# lamloei_app_a092508.net
KiCad netlist of a schematic drawn in EAGLE
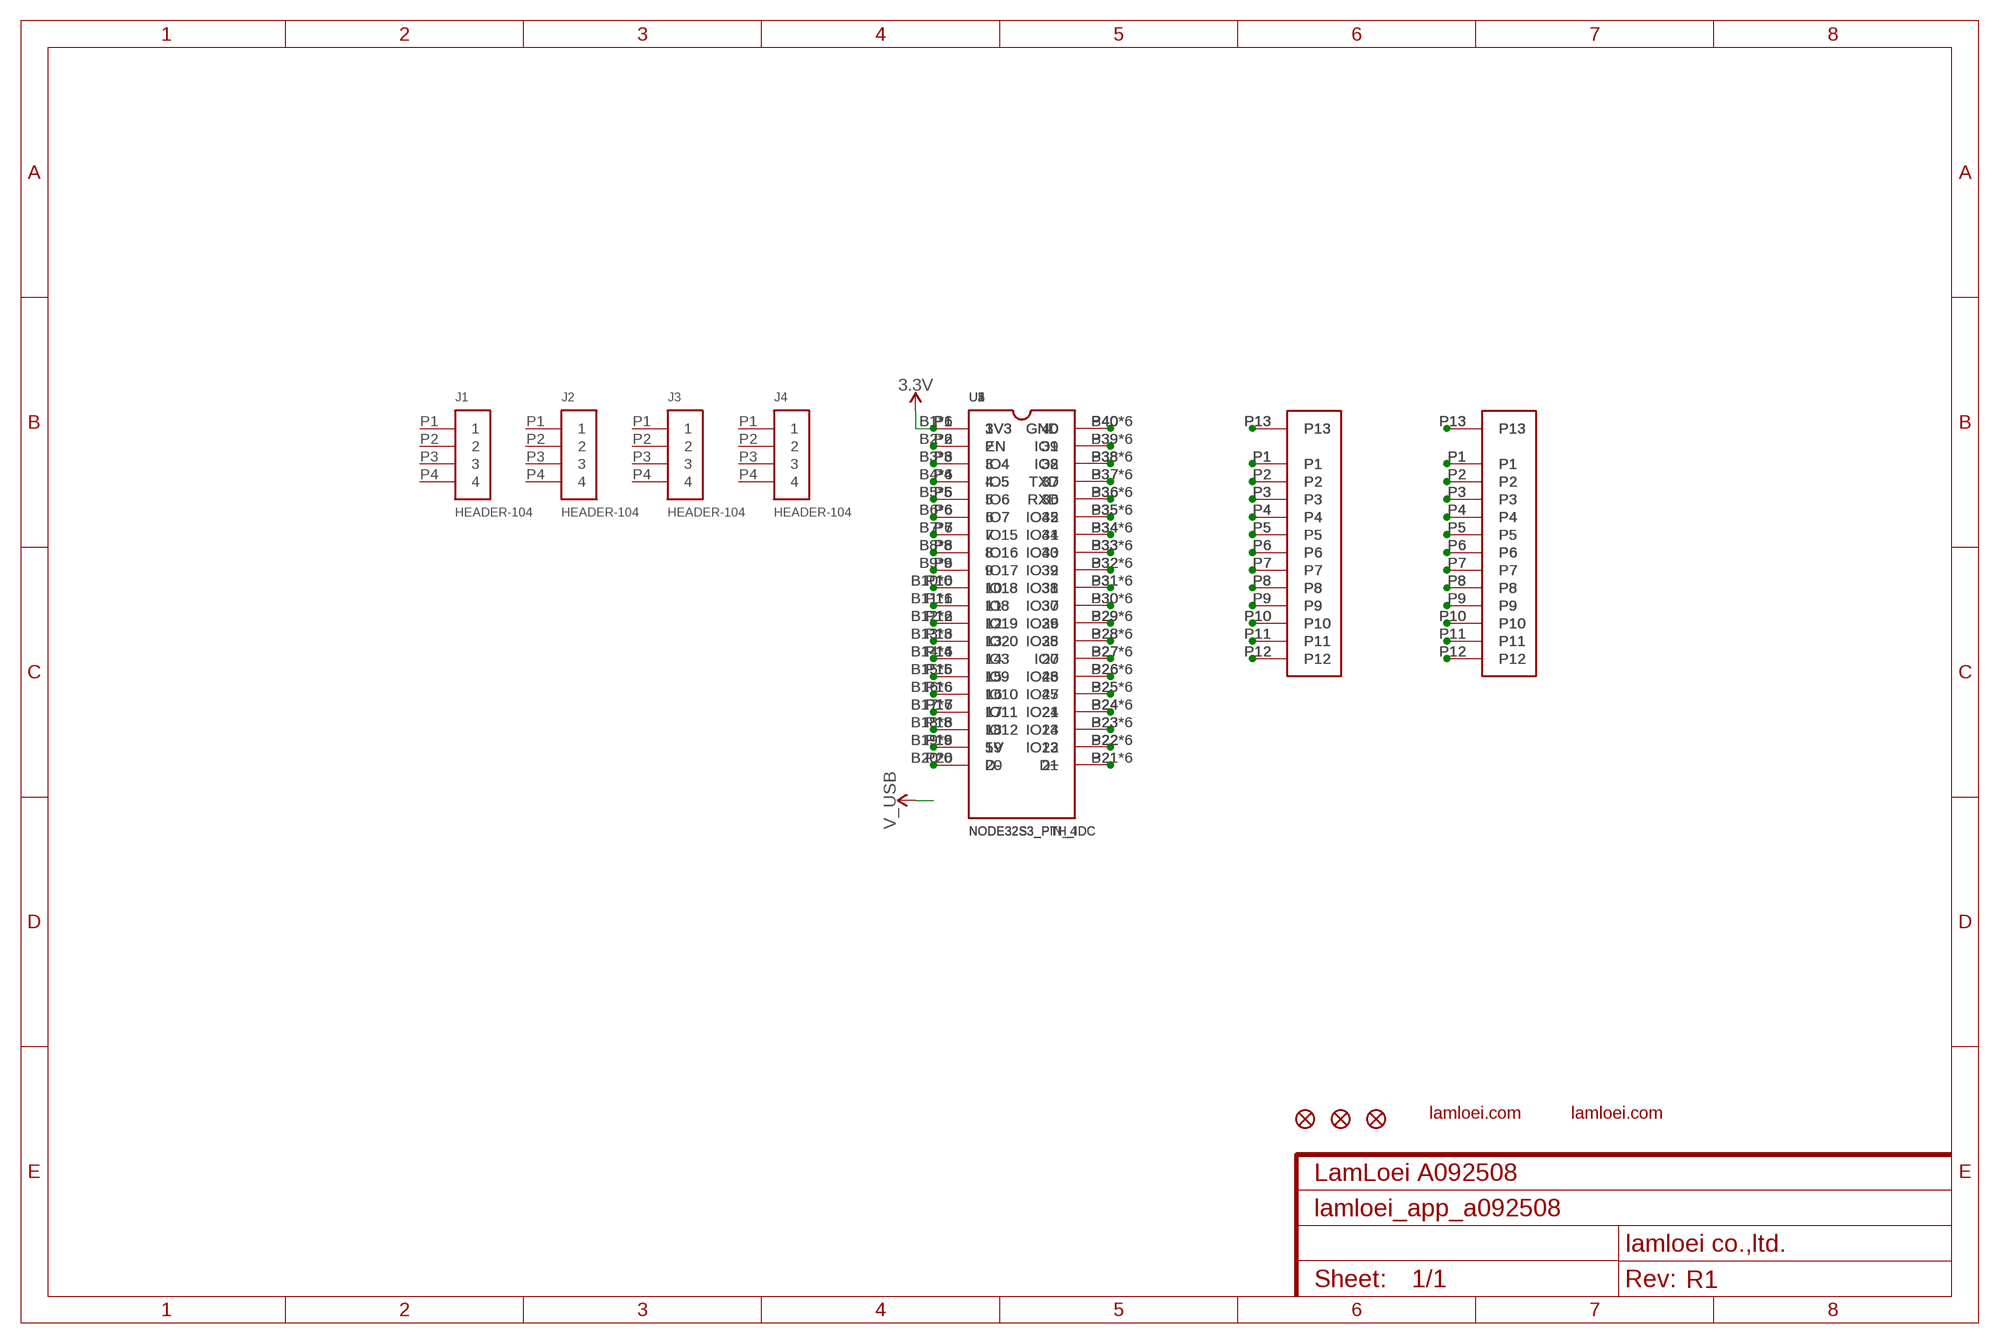
[diagram p0: schematic, sheet 1]

(export (version "E")
  (design (tool "Eeschema 10.0.6"))
  (components
    (comp (ref "J1")
      (value "HEADER-104")
      (footprint "eagle-import:HEADER-104")
      (libsource (lib "eagle-import") (part "HEADER-104"))
    )
    (comp (ref "J2")
      (value "HEADER-104")
      (footprint "eagle-import:HEADER-104")
      (libsource (lib "eagle-import") (part "HEADER-104"))
    )
    (comp (ref "J3")
      (value "HEADER-104")
      (footprint "eagle-import:HEADER-104")
      (libsource (lib "eagle-import") (part "HEADER-104"))
    )
    (comp (ref "J4")
      (value "HEADER-104")
      (footprint "eagle-import:HEADER-104")
      (libsource (lib "eagle-import") (part "HEADER-104"))
    )
    (comp (ref "U1")
      (value "NODE32S3_PIN_4")
      (footprint "eagle-import:NODE32S3_PTH_4")
      (libsource (lib "eagle-import") (part "NODE32S3_PIN_4"))
    )
    (comp (ref "U2")
      (value "NODE32S3_PIN_4")
      (footprint "eagle-import:NODE32S3_PTH_4")
      (libsource (lib "eagle-import") (part "NODE32S3_PIN_4"))
    )
    (comp (ref "U3")
      (value "NODE32S3_PTH_IDC")
      (footprint "eagle-import:NODE32S3_PTH_IDC")
      (libsource (lib "eagle-import") (part "NODE32S3_PTH_IDC"))
    )
    (comp (ref "U4")
      (value "NODE32S3_PTH_IDC")
      (footprint "eagle-import:NODE32S3_PTH_IDC")
      (libsource (lib "eagle-import") (part "NODE32S3_PTH_IDC"))
    )
    (comp (ref "U5")
      (value "NODE32S3_PTH_IDC")
      (footprint "eagle-import:NODE32S3_PTH_IDC")
      (libsource (lib "eagle-import") (part "NODE32S3_PTH_IDC"))
    )
    (comp (ref "X1")
      (value "5EHDRC-12P-508")
      (footprint "eagle-import:5EHDRC-12P-508")
      (libsource (lib "eagle-import") (part "5EHDRC-12P-508"))
    )
    (comp (ref "X2")
      (value "5EHDRC-12P-5.08MM")
      (footprint "eagle-import:5EHDRC-12P-5.08MM")
      (libsource (lib "eagle-import") (part "5EHDRC-12P-5.08MM"))
    )
    (comp (ref "X3")
      (value "5EHDRC-12P-2-508")
      (footprint "eagle-import:5EHDRC-12P-2-508")
      (libsource (lib "eagle-import") (part "5EHDRC-12P-2-508"))
    )
    (comp (ref "X4")
      (value "5EHDRC-12P-508")
      (footprint "eagle-import:5EHDRC-12P-508")
      (libsource (lib "eagle-import") (part "5EHDRC-12P-508"))
    )
    (comp (ref "X5")
      (value "5EHDRC-12P-5.08MM")
      (footprint "eagle-import:5EHDRC-12P-5.08MM")
      (libsource (lib "eagle-import") (part "5EHDRC-12P-5.08MM"))
    )
    (comp (ref "X6")
      (value "5EHDRC-12P-2-508")
      (footprint "eagle-import:5EHDRC-12P-2-508")
      (libsource (lib "eagle-import") (part "5EHDRC-12P-2-508"))
    )
    (comp (ref "ZFD1")
      (value "FIDUCIAL1X2")
      (footprint "eagle-import:FIDUCIAL-1X2")
      (libsource (lib "eagle-import") (part "FIDUCIAL1X2"))
    )
    (comp (ref "ZFD2")
      (value "FIDUCIAL1X2")
      (footprint "eagle-import:FIDUCIAL-1X2")
      (libsource (lib "eagle-import") (part "FIDUCIAL1X2"))
    )
    (comp (ref "ZFD3")
      (value "FIDUCIAL1X2")
      (footprint "eagle-import:FIDUCIAL-1X2")
      (libsource (lib "eagle-import") (part "FIDUCIAL1X2"))
    )
    (comp (ref "ZL1")
      (value "LAMLEOI_LOGO_3")
      (footprint "eagle-import:LAMLEOI_LOGO_3")
      (libsource (lib "eagle-import") (part "LAMLEOI_LOGO_3"))
    )
    (comp (ref "ZL2")
      (value "LAMLEOI_LOGO_3")
      (footprint "eagle-import:LAMLEOI_LOGO_3")
      (libsource (lib "eagle-import") (part "LAMLEOI_LOGO_3"))
    )
  )
  (nets
    (net (code "1") (name "3.3V") (class "Default")
      (node (ref "U1") (pin "B1") (pinfunction "1_B1") (pintype "bidirectional"))
      (node (ref "U1") (pin "N1") (pinfunction "1_N1") (pintype "bidirectional"))
      (node (ref "U1") (pin "O1") (pinfunction "1_O1") (pintype "bidirectional"))
      (node (ref "U1") (pin "P1") (pinfunction "1_P1") (pintype "bidirectional"))
      (node (ref "U1") (pin "Q1") (pinfunction "1_Q1") (pintype "bidirectional"))
      (node (ref "U1") (pin "T1") (pinfunction "1_T1") (pintype "bidirectional"))
      (node (ref "U2") (pin "B1") (pinfunction "1_B1") (pintype "bidirectional"))
      (node (ref "U2") (pin "N1") (pinfunction "1_N1") (pintype "bidirectional"))
      (node (ref "U2") (pin "O1") (pinfunction "1_O1") (pintype "bidirectional"))
      (node (ref "U2") (pin "P1") (pinfunction "1_P1") (pintype "bidirectional"))
      (node (ref "U2") (pin "Q1") (pinfunction "1_Q1") (pintype "bidirectional"))
      (node (ref "U2") (pin "T1") (pinfunction "1_T1") (pintype "bidirectional"))
      (node (ref "U3") (pin "P1") (pinfunction "3V3_P1") (pintype "bidirectional"))
      (node (ref "U4") (pin "P1") (pinfunction "3V3_P1") (pintype "bidirectional"))
      (node (ref "U5") (pin "P1") (pinfunction "3V3_P1") (pintype "bidirectional"))
    )
    (net (code "2") (name "Net-(U3-5V)") (class "Default")
      (node (ref "U1") (pin "B19") (pinfunction "19_B19") (pintype "bidirectional"))
      (node (ref "U1") (pin "N19") (pinfunction "19_N19") (pintype "bidirectional"))
      (node (ref "U1") (pin "O19") (pinfunction "19_O19") (pintype "bidirectional"))
      (node (ref "U1") (pin "P19") (pinfunction "19_P19") (pintype "bidirectional"))
      (node (ref "U1") (pin "Q19") (pinfunction "19_Q19") (pintype "bidirectional"))
      (node (ref "U1") (pin "T19") (pinfunction "19_T19") (pintype "bidirectional"))
      (node (ref "U2") (pin "B19") (pinfunction "19_B19") (pintype "bidirectional"))
      (node (ref "U2") (pin "N19") (pinfunction "19_N19") (pintype "bidirectional"))
      (node (ref "U2") (pin "O19") (pinfunction "19_O19") (pintype "bidirectional"))
      (node (ref "U2") (pin "P19") (pinfunction "19_P19") (pintype "bidirectional"))
      (node (ref "U2") (pin "Q19") (pinfunction "19_Q19") (pintype "bidirectional"))
      (node (ref "U2") (pin "T19") (pinfunction "19_T19") (pintype "bidirectional"))
      (node (ref "U3") (pin "P19") (pinfunction "5V_P19") (pintype "bidirectional"))
      (node (ref "U4") (pin "P19") (pinfunction "5V_P19") (pintype "bidirectional"))
      (node (ref "U5") (pin "P19") (pinfunction "5V_P19") (pintype "bidirectional"))
    )
    (net (code "3") (name "Net-(U3-D+)") (class "Default")
      (node (ref "U1") (pin "B21") (pinfunction "21_B21") (pintype "bidirectional"))
      (node (ref "U1") (pin "N21") (pinfunction "21_N21") (pintype "bidirectional"))
      (node (ref "U1") (pin "O21") (pinfunction "21_O21") (pintype "bidirectional"))
      (node (ref "U1") (pin "P21") (pinfunction "21_P21") (pintype "bidirectional"))
      (node (ref "U1") (pin "Q21") (pinfunction "21_Q21") (pintype "bidirectional"))
      (node (ref "U1") (pin "T21") (pinfunction "21_T21") (pintype "bidirectional"))
      (node (ref "U2") (pin "B21") (pinfunction "21_B21") (pintype "bidirectional"))
      (node (ref "U2") (pin "N21") (pinfunction "21_N21") (pintype "bidirectional"))
      (node (ref "U2") (pin "O21") (pinfunction "21_O21") (pintype "bidirectional"))
      (node (ref "U2") (pin "P21") (pinfunction "21_P21") (pintype "bidirectional"))
      (node (ref "U2") (pin "Q21") (pinfunction "21_Q21") (pintype "bidirectional"))
      (node (ref "U2") (pin "T21") (pinfunction "21_T21") (pintype "bidirectional"))
      (node (ref "U3") (pin "P21") (pinfunction "D+_P21") (pintype "bidirectional"))
      (node (ref "U4") (pin "P21") (pinfunction "D+_P21") (pintype "bidirectional"))
      (node (ref "U5") (pin "P21") (pinfunction "D+_P21") (pintype "bidirectional"))
    )
    (net (code "4") (name "Net-(U3-D-)") (class "Default")
      (node (ref "U1") (pin "B20") (pinfunction "20_B20") (pintype "bidirectional"))
      (node (ref "U1") (pin "N20") (pinfunction "20_N20") (pintype "bidirectional"))
      (node (ref "U1") (pin "O20") (pinfunction "20_O20") (pintype "bidirectional"))
      (node (ref "U1") (pin "P20") (pinfunction "20_P20") (pintype "bidirectional"))
      (node (ref "U1") (pin "Q20") (pinfunction "20_Q20") (pintype "bidirectional"))
      (node (ref "U1") (pin "T20") (pinfunction "20_T20") (pintype "bidirectional"))
      (node (ref "U2") (pin "B20") (pinfunction "20_B20") (pintype "bidirectional"))
      (node (ref "U2") (pin "N20") (pinfunction "20_N20") (pintype "bidirectional"))
      (node (ref "U2") (pin "O20") (pinfunction "20_O20") (pintype "bidirectional"))
      (node (ref "U2") (pin "P20") (pinfunction "20_P20") (pintype "bidirectional"))
      (node (ref "U2") (pin "Q20") (pinfunction "20_Q20") (pintype "bidirectional"))
      (node (ref "U2") (pin "T20") (pinfunction "20_T20") (pintype "bidirectional"))
      (node (ref "U3") (pin "P20") (pinfunction "D-_P20") (pintype "bidirectional"))
      (node (ref "U4") (pin "P20") (pinfunction "D-_P20") (pintype "bidirectional"))
      (node (ref "U5") (pin "P20") (pinfunction "D-_P20") (pintype "bidirectional"))
    )
    (net (code "5") (name "Net-(U3-EN)") (class "Default")
      (node (ref "U1") (pin "B2") (pinfunction "2_B2") (pintype "bidirectional"))
      (node (ref "U1") (pin "N2") (pinfunction "2_N2") (pintype "bidirectional"))
      (node (ref "U1") (pin "O2") (pinfunction "2_O2") (pintype "bidirectional"))
      (node (ref "U1") (pin "P2") (pinfunction "2_P2") (pintype "bidirectional"))
      (node (ref "U1") (pin "Q2") (pinfunction "2_Q2") (pintype "bidirectional"))
      (node (ref "U1") (pin "T2") (pinfunction "2_T2") (pintype "bidirectional"))
      (node (ref "U2") (pin "B2") (pinfunction "2_B2") (pintype "bidirectional"))
      (node (ref "U2") (pin "N2") (pinfunction "2_N2") (pintype "bidirectional"))
      (node (ref "U2") (pin "O2") (pinfunction "2_O2") (pintype "bidirectional"))
      (node (ref "U2") (pin "P2") (pinfunction "2_P2") (pintype "bidirectional"))
      (node (ref "U2") (pin "Q2") (pinfunction "2_Q2") (pintype "bidirectional"))
      (node (ref "U2") (pin "T2") (pinfunction "2_T2") (pintype "bidirectional"))
      (node (ref "U3") (pin "P2") (pinfunction "EN_P2") (pintype "bidirectional"))
      (node (ref "U4") (pin "P2") (pinfunction "EN_P2") (pintype "bidirectional"))
      (node (ref "U5") (pin "P2") (pinfunction "EN_P2") (pintype "bidirectional"))
    )
    (net (code "6") (name "Net-(U3-GND)") (class "Default")
      (node (ref "U1") (pin "B40") (pinfunction "40_B40") (pintype "bidirectional"))
      (node (ref "U1") (pin "N40") (pinfunction "40_N40") (pintype "bidirectional"))
      (node (ref "U1") (pin "O40") (pinfunction "40_O40") (pintype "bidirectional"))
      (node (ref "U1") (pin "P40") (pinfunction "40_P40") (pintype "bidirectional"))
      (node (ref "U1") (pin "Q40") (pinfunction "40_Q40") (pintype "bidirectional"))
      (node (ref "U1") (pin "T40") (pinfunction "40_T40") (pintype "bidirectional"))
      (node (ref "U2") (pin "B40") (pinfunction "40_B40") (pintype "bidirectional"))
      (node (ref "U2") (pin "N40") (pinfunction "40_N40") (pintype "bidirectional"))
      (node (ref "U2") (pin "O40") (pinfunction "40_O40") (pintype "bidirectional"))
      (node (ref "U2") (pin "P40") (pinfunction "40_P40") (pintype "bidirectional"))
      (node (ref "U2") (pin "Q40") (pinfunction "40_Q40") (pintype "bidirectional"))
      (node (ref "U2") (pin "T40") (pinfunction "40_T40") (pintype "bidirectional"))
      (node (ref "U3") (pin "P40") (pinfunction "GND_P40") (pintype "bidirectional"))
      (node (ref "U4") (pin "P40") (pinfunction "GND_P40") (pintype "bidirectional"))
      (node (ref "U5") (pin "P40") (pinfunction "GND_P40") (pintype "bidirectional"))
    )
    (net (code "7") (name "Net-(U3-IO0)") (class "Default")
      (node (ref "U1") (pin "B27") (pinfunction "27_B27") (pintype "bidirectional"))
      (node (ref "U1") (pin "N27") (pinfunction "27_N27") (pintype "bidirectional"))
      (node (ref "U1") (pin "O27") (pinfunction "27_O27") (pintype "bidirectional"))
      (node (ref "U1") (pin "P27") (pinfunction "27_P27") (pintype "bidirectional"))
      (node (ref "U1") (pin "Q27") (pinfunction "27_Q27") (pintype "bidirectional"))
      (node (ref "U1") (pin "T27") (pinfunction "27_T27") (pintype "bidirectional"))
      (node (ref "U2") (pin "B27") (pinfunction "27_B27") (pintype "bidirectional"))
      (node (ref "U2") (pin "N27") (pinfunction "27_N27") (pintype "bidirectional"))
      (node (ref "U2") (pin "O27") (pinfunction "27_O27") (pintype "bidirectional"))
      (node (ref "U2") (pin "P27") (pinfunction "27_P27") (pintype "bidirectional"))
      (node (ref "U2") (pin "Q27") (pinfunction "27_Q27") (pintype "bidirectional"))
      (node (ref "U2") (pin "T27") (pinfunction "27_T27") (pintype "bidirectional"))
      (node (ref "U3") (pin "P27") (pinfunction "IO0_P27") (pintype "bidirectional"))
      (node (ref "U4") (pin "P27") (pinfunction "IO0_P27") (pintype "bidirectional"))
      (node (ref "U5") (pin "P27") (pinfunction "IO0_P27") (pintype "bidirectional"))
    )
    (net (code "8") (name "Net-(U3-IO1)") (class "Default")
      (node (ref "U1") (pin "B39") (pinfunction "39_B39") (pintype "bidirectional"))
      (node (ref "U1") (pin "N39") (pinfunction "39_N39") (pintype "bidirectional"))
      (node (ref "U1") (pin "O39") (pinfunction "39_O39") (pintype "bidirectional"))
      (node (ref "U1") (pin "P39") (pinfunction "39_P39") (pintype "bidirectional"))
      (node (ref "U1") (pin "Q39") (pinfunction "39_Q39") (pintype "bidirectional"))
      (node (ref "U1") (pin "T39") (pinfunction "39_T39") (pintype "bidirectional"))
      (node (ref "U2") (pin "B39") (pinfunction "39_B39") (pintype "bidirectional"))
      (node (ref "U2") (pin "N39") (pinfunction "39_N39") (pintype "bidirectional"))
      (node (ref "U2") (pin "O39") (pinfunction "39_O39") (pintype "bidirectional"))
      (node (ref "U2") (pin "P39") (pinfunction "39_P39") (pintype "bidirectional"))
      (node (ref "U2") (pin "Q39") (pinfunction "39_Q39") (pintype "bidirectional"))
      (node (ref "U2") (pin "T39") (pinfunction "39_T39") (pintype "bidirectional"))
      (node (ref "U3") (pin "P39") (pinfunction "IO1_P39") (pintype "bidirectional"))
      (node (ref "U4") (pin "P39") (pinfunction "IO1_P39") (pintype "bidirectional"))
      (node (ref "U5") (pin "P39") (pinfunction "IO1_P39") (pintype "bidirectional"))
    )
    (net (code "9") (name "Net-(U3-IO2)") (class "Default")
      (node (ref "U1") (pin "B38") (pinfunction "38_B38") (pintype "bidirectional"))
      (node (ref "U1") (pin "N38") (pinfunction "38_N38") (pintype "bidirectional"))
      (node (ref "U1") (pin "O38") (pinfunction "38_O38") (pintype "bidirectional"))
      (node (ref "U1") (pin "P38") (pinfunction "38_P38") (pintype "bidirectional"))
      (node (ref "U1") (pin "Q38") (pinfunction "38_Q38") (pintype "bidirectional"))
      (node (ref "U1") (pin "T38") (pinfunction "38_T38") (pintype "bidirectional"))
      (node (ref "U2") (pin "B38") (pinfunction "38_B38") (pintype "bidirectional"))
      (node (ref "U2") (pin "N38") (pinfunction "38_N38") (pintype "bidirectional"))
      (node (ref "U2") (pin "O38") (pinfunction "38_O38") (pintype "bidirectional"))
      (node (ref "U2") (pin "P38") (pinfunction "38_P38") (pintype "bidirectional"))
      (node (ref "U2") (pin "Q38") (pinfunction "38_Q38") (pintype "bidirectional"))
      (node (ref "U2") (pin "T38") (pinfunction "38_T38") (pintype "bidirectional"))
      (node (ref "U3") (pin "P38") (pinfunction "IO2_P38") (pintype "bidirectional"))
      (node (ref "U4") (pin "P38") (pinfunction "IO2_P38") (pintype "bidirectional"))
      (node (ref "U5") (pin "P38") (pinfunction "IO2_P38") (pintype "bidirectional"))
    )
    (net (code "10") (name "Net-(U3-IO3)") (class "Default")
      (node (ref "U1") (pin "B14") (pinfunction "14_B14") (pintype "bidirectional"))
      (node (ref "U1") (pin "N14") (pinfunction "14_N14") (pintype "bidirectional"))
      (node (ref "U1") (pin "O14") (pinfunction "14_O14") (pintype "bidirectional"))
      (node (ref "U1") (pin "P14") (pinfunction "14_P14") (pintype "bidirectional"))
      (node (ref "U1") (pin "Q14") (pinfunction "14_Q14") (pintype "bidirectional"))
      (node (ref "U1") (pin "T14") (pinfunction "14_T14") (pintype "bidirectional"))
      (node (ref "U2") (pin "B14") (pinfunction "14_B14") (pintype "bidirectional"))
      (node (ref "U2") (pin "N14") (pinfunction "14_N14") (pintype "bidirectional"))
      (node (ref "U2") (pin "O14") (pinfunction "14_O14") (pintype "bidirectional"))
      (node (ref "U2") (pin "P14") (pinfunction "14_P14") (pintype "bidirectional"))
      (node (ref "U2") (pin "Q14") (pinfunction "14_Q14") (pintype "bidirectional"))
      (node (ref "U2") (pin "T14") (pinfunction "14_T14") (pintype "bidirectional"))
      (node (ref "U3") (pin "P14") (pinfunction "IO3_P14") (pintype "bidirectional"))
      (node (ref "U4") (pin "P14") (pinfunction "IO3_P14") (pintype "bidirectional"))
      (node (ref "U5") (pin "P14") (pinfunction "IO3_P14") (pintype "bidirectional"))
    )
    (net (code "11") (name "Net-(U3-IO4)") (class "Default")
      (node (ref "U1") (pin "B3") (pinfunction "3_B3") (pintype "bidirectional"))
      (node (ref "U1") (pin "N3") (pinfunction "3_N3") (pintype "bidirectional"))
      (node (ref "U1") (pin "O3") (pinfunction "3_O3") (pintype "bidirectional"))
      (node (ref "U1") (pin "P3") (pinfunction "3_P3") (pintype "bidirectional"))
      (node (ref "U1") (pin "Q3") (pinfunction "3_Q3") (pintype "bidirectional"))
      (node (ref "U1") (pin "T3") (pinfunction "3_T3") (pintype "bidirectional"))
      (node (ref "U2") (pin "B3") (pinfunction "3_B3") (pintype "bidirectional"))
      (node (ref "U2") (pin "N3") (pinfunction "3_N3") (pintype "bidirectional"))
      (node (ref "U2") (pin "O3") (pinfunction "3_O3") (pintype "bidirectional"))
      (node (ref "U2") (pin "P3") (pinfunction "3_P3") (pintype "bidirectional"))
      (node (ref "U2") (pin "Q3") (pinfunction "3_Q3") (pintype "bidirectional"))
      (node (ref "U2") (pin "T3") (pinfunction "3_T3") (pintype "bidirectional"))
      (node (ref "U3") (pin "P3") (pinfunction "IO4_P3") (pintype "bidirectional"))
      (node (ref "U4") (pin "P3") (pinfunction "IO4_P3") (pintype "bidirectional"))
      (node (ref "U5") (pin "P3") (pinfunction "IO4_P3") (pintype "bidirectional"))
    )
    (net (code "12") (name "Net-(U3-IO5)") (class "Default")
      (node (ref "U1") (pin "B4") (pinfunction "4_B4") (pintype "bidirectional"))
      (node (ref "U1") (pin "N4") (pinfunction "4_N4") (pintype "bidirectional"))
      (node (ref "U1") (pin "O4") (pinfunction "4_O4") (pintype "bidirectional"))
      (node (ref "U1") (pin "P4") (pinfunction "4_P4") (pintype "bidirectional"))
      (node (ref "U1") (pin "Q4") (pinfunction "4_Q4") (pintype "bidirectional"))
      (node (ref "U1") (pin "T4") (pinfunction "4_T4") (pintype "bidirectional"))
      (node (ref "U2") (pin "B4") (pinfunction "4_B4") (pintype "bidirectional"))
      (node (ref "U2") (pin "N4") (pinfunction "4_N4") (pintype "bidirectional"))
      (node (ref "U2") (pin "O4") (pinfunction "4_O4") (pintype "bidirectional"))
      (node (ref "U2") (pin "P4") (pinfunction "4_P4") (pintype "bidirectional"))
      (node (ref "U2") (pin "Q4") (pinfunction "4_Q4") (pintype "bidirectional"))
      (node (ref "U2") (pin "T4") (pinfunction "4_T4") (pintype "bidirectional"))
      (node (ref "U3") (pin "P4") (pinfunction "IO5_P4") (pintype "bidirectional"))
      (node (ref "U4") (pin "P4") (pinfunction "IO5_P4") (pintype "bidirectional"))
      (node (ref "U5") (pin "P4") (pinfunction "IO5_P4") (pintype "bidirectional"))
    )
    (net (code "13") (name "Net-(U3-IO6)") (class "Default")
      (node (ref "U1") (pin "B5") (pinfunction "5_B5") (pintype "bidirectional"))
      (node (ref "U1") (pin "N5") (pinfunction "5_N5") (pintype "bidirectional"))
      (node (ref "U1") (pin "O5") (pinfunction "5_O5") (pintype "bidirectional"))
      (node (ref "U1") (pin "P5") (pinfunction "5_P5") (pintype "bidirectional"))
      (node (ref "U1") (pin "Q5") (pinfunction "5_Q5") (pintype "bidirectional"))
      (node (ref "U1") (pin "T5") (pinfunction "5_T5") (pintype "bidirectional"))
      (node (ref "U2") (pin "B5") (pinfunction "5_B5") (pintype "bidirectional"))
      (node (ref "U2") (pin "N5") (pinfunction "5_N5") (pintype "bidirectional"))
      (node (ref "U2") (pin "O5") (pinfunction "5_O5") (pintype "bidirectional"))
      (node (ref "U2") (pin "P5") (pinfunction "5_P5") (pintype "bidirectional"))
      (node (ref "U2") (pin "Q5") (pinfunction "5_Q5") (pintype "bidirectional"))
      (node (ref "U2") (pin "T5") (pinfunction "5_T5") (pintype "bidirectional"))
      (node (ref "U3") (pin "P5") (pinfunction "IO6_P5") (pintype "bidirectional"))
      (node (ref "U4") (pin "P5") (pinfunction "IO6_P5") (pintype "bidirectional"))
      (node (ref "U5") (pin "P5") (pinfunction "IO6_P5") (pintype "bidirectional"))
    )
    (net (code "14") (name "Net-(U3-IO7)") (class "Default")
      (node (ref "U1") (pin "B6") (pinfunction "6_B6") (pintype "bidirectional"))
      (node (ref "U1") (pin "N6") (pinfunction "6_N6") (pintype "bidirectional"))
      (node (ref "U1") (pin "O6") (pinfunction "6_O6") (pintype "bidirectional"))
      (node (ref "U1") (pin "P6") (pinfunction "6_P6") (pintype "bidirectional"))
      (node (ref "U1") (pin "Q6") (pinfunction "6_Q6") (pintype "bidirectional"))
      (node (ref "U1") (pin "T6") (pinfunction "6_T6") (pintype "bidirectional"))
      (node (ref "U2") (pin "B6") (pinfunction "6_B6") (pintype "bidirectional"))
      (node (ref "U2") (pin "N6") (pinfunction "6_N6") (pintype "bidirectional"))
      (node (ref "U2") (pin "O6") (pinfunction "6_O6") (pintype "bidirectional"))
      (node (ref "U2") (pin "P6") (pinfunction "6_P6") (pintype "bidirectional"))
      (node (ref "U2") (pin "Q6") (pinfunction "6_Q6") (pintype "bidirectional"))
      (node (ref "U2") (pin "T6") (pinfunction "6_T6") (pintype "bidirectional"))
      (node (ref "U3") (pin "P6") (pinfunction "IO7_P6") (pintype "bidirectional"))
      (node (ref "U4") (pin "P6") (pinfunction "IO7_P6") (pintype "bidirectional"))
      (node (ref "U5") (pin "P6") (pinfunction "IO7_P6") (pintype "bidirectional"))
    )
    (net (code "15") (name "Net-(U3-IO8)") (class "Default")
      (node (ref "U1") (pin "B11") (pinfunction "11_B11") (pintype "bidirectional"))
      (node (ref "U1") (pin "N11") (pinfunction "11_N11") (pintype "bidirectional"))
      (node (ref "U1") (pin "O11") (pinfunction "11_O11") (pintype "bidirectional"))
      (node (ref "U1") (pin "P11") (pinfunction "11_P11") (pintype "bidirectional"))
      (node (ref "U1") (pin "Q11") (pinfunction "11_Q11") (pintype "bidirectional"))
      (node (ref "U1") (pin "T11") (pinfunction "11_T11") (pintype "bidirectional"))
      (node (ref "U2") (pin "B11") (pinfunction "11_B11") (pintype "bidirectional"))
      (node (ref "U2") (pin "N11") (pinfunction "11_N11") (pintype "bidirectional"))
      (node (ref "U2") (pin "O11") (pinfunction "11_O11") (pintype "bidirectional"))
      (node (ref "U2") (pin "P11") (pinfunction "11_P11") (pintype "bidirectional"))
      (node (ref "U2") (pin "Q11") (pinfunction "11_Q11") (pintype "bidirectional"))
      (node (ref "U2") (pin "T11") (pinfunction "11_T11") (pintype "bidirectional"))
      (node (ref "U3") (pin "P11") (pinfunction "IO8_P11") (pintype "bidirectional"))
      (node (ref "U4") (pin "P11") (pinfunction "IO8_P11") (pintype "bidirectional"))
      (node (ref "U5") (pin "P11") (pinfunction "IO8_P11") (pintype "bidirectional"))
    )
    (net (code "16") (name "Net-(U3-IO9)") (class "Default")
      (node (ref "U1") (pin "B15") (pinfunction "15_B15") (pintype "bidirectional"))
      (node (ref "U1") (pin "N15") (pinfunction "15_N15") (pintype "bidirectional"))
      (node (ref "U1") (pin "O15") (pinfunction "15_O15") (pintype "bidirectional"))
      (node (ref "U1") (pin "P15") (pinfunction "15_P15") (pintype "bidirectional"))
      (node (ref "U1") (pin "Q15") (pinfunction "15_Q15") (pintype "bidirectional"))
      (node (ref "U1") (pin "T15") (pinfunction "15_T15") (pintype "bidirectional"))
      (node (ref "U2") (pin "B15") (pinfunction "15_B15") (pintype "bidirectional"))
      (node (ref "U2") (pin "N15") (pinfunction "15_N15") (pintype "bidirectional"))
      (node (ref "U2") (pin "O15") (pinfunction "15_O15") (pintype "bidirectional"))
      (node (ref "U2") (pin "P15") (pinfunction "15_P15") (pintype "bidirectional"))
      (node (ref "U2") (pin "Q15") (pinfunction "15_Q15") (pintype "bidirectional"))
      (node (ref "U2") (pin "T15") (pinfunction "15_T15") (pintype "bidirectional"))
      (node (ref "U3") (pin "P15") (pinfunction "IO9_P15") (pintype "bidirectional"))
      (node (ref "U4") (pin "P15") (pinfunction "IO9_P15") (pintype "bidirectional"))
      (node (ref "U5") (pin "P15") (pinfunction "IO9_P15") (pintype "bidirectional"))
    )
    (net (code "17") (name "Net-(U3-IO10)") (class "Default")
      (node (ref "U1") (pin "B16") (pinfunction "16_B16") (pintype "bidirectional"))
      (node (ref "U1") (pin "N16") (pinfunction "16_N16") (pintype "bidirectional"))
      (node (ref "U1") (pin "O16") (pinfunction "16_O16") (pintype "bidirectional"))
      (node (ref "U1") (pin "P16") (pinfunction "16_P16") (pintype "bidirectional"))
      (node (ref "U1") (pin "Q16") (pinfunction "16_Q16") (pintype "bidirectional"))
      (node (ref "U1") (pin "T16") (pinfunction "16_T16") (pintype "bidirectional"))
      (node (ref "U2") (pin "B16") (pinfunction "16_B16") (pintype "bidirectional"))
      (node (ref "U2") (pin "N16") (pinfunction "16_N16") (pintype "bidirectional"))
      (node (ref "U2") (pin "O16") (pinfunction "16_O16") (pintype "bidirectional"))
      (node (ref "U2") (pin "P16") (pinfunction "16_P16") (pintype "bidirectional"))
      (node (ref "U2") (pin "Q16") (pinfunction "16_Q16") (pintype "bidirectional"))
      (node (ref "U2") (pin "T16") (pinfunction "16_T16") (pintype "bidirectional"))
      (node (ref "U3") (pin "P16") (pinfunction "IO10_P16") (pintype "bidirectional"))
      (node (ref "U4") (pin "P16") (pinfunction "IO10_P16") (pintype "bidirectional"))
      (node (ref "U5") (pin "P16") (pinfunction "IO10_P16") (pintype "bidirectional"))
    )
    (net (code "18") (name "Net-(U3-IO11)") (class "Default")
      (node (ref "U1") (pin "B17") (pinfunction "17_B17") (pintype "bidirectional"))
      (node (ref "U1") (pin "N17") (pinfunction "17_N17") (pintype "bidirectional"))
      (node (ref "U1") (pin "O17") (pinfunction "17_O17") (pintype "bidirectional"))
      (node (ref "U1") (pin "P17") (pinfunction "17_P17") (pintype "bidirectional"))
      (node (ref "U1") (pin "Q17") (pinfunction "17_Q17") (pintype "bidirectional"))
      (node (ref "U1") (pin "T17") (pinfunction "17_T17") (pintype "bidirectional"))
      (node (ref "U2") (pin "B17") (pinfunction "17_B17") (pintype "bidirectional"))
      (node (ref "U2") (pin "N17") (pinfunction "17_N17") (pintype "bidirectional"))
      (node (ref "U2") (pin "O17") (pinfunction "17_O17") (pintype "bidirectional"))
      (node (ref "U2") (pin "P17") (pinfunction "17_P17") (pintype "bidirectional"))
      (node (ref "U2") (pin "Q17") (pinfunction "17_Q17") (pintype "bidirectional"))
      (node (ref "U2") (pin "T17") (pinfunction "17_T17") (pintype "bidirectional"))
      (node (ref "U3") (pin "P17") (pinfunction "IO11_P17") (pintype "bidirectional"))
      (node (ref "U4") (pin "P17") (pinfunction "IO11_P17") (pintype "bidirectional"))
      (node (ref "U5") (pin "P17") (pinfunction "IO11_P17") (pintype "bidirectional"))
    )
    (net (code "19") (name "Net-(U3-IO12)") (class "Default")
      (node (ref "U1") (pin "B18") (pinfunction "18_B18") (pintype "bidirectional"))
      (node (ref "U1") (pin "N18") (pinfunction "18_N18") (pintype "bidirectional"))
      (node (ref "U1") (pin "O18") (pinfunction "18_O18") (pintype "bidirectional"))
      (node (ref "U1") (pin "P18") (pinfunction "18_P18") (pintype "bidirectional"))
      (node (ref "U1") (pin "Q18") (pinfunction "18_Q18") (pintype "bidirectional"))
      (node (ref "U1") (pin "T18") (pinfunction "18_T18") (pintype "bidirectional"))
      (node (ref "U2") (pin "B18") (pinfunction "18_B18") (pintype "bidirectional"))
      (node (ref "U2") (pin "N18") (pinfunction "18_N18") (pintype "bidirectional"))
      (node (ref "U2") (pin "O18") (pinfunction "18_O18") (pintype "bidirectional"))
      (node (ref "U2") (pin "P18") (pinfunction "18_P18") (pintype "bidirectional"))
      (node (ref "U2") (pin "Q18") (pinfunction "18_Q18") (pintype "bidirectional"))
      (node (ref "U2") (pin "T18") (pinfunction "18_T18") (pintype "bidirectional"))
      (node (ref "U3") (pin "P18") (pinfunction "IO12_P18") (pintype "bidirectional"))
      (node (ref "U4") (pin "P18") (pinfunction "IO12_P18") (pintype "bidirectional"))
      (node (ref "U5") (pin "P18") (pinfunction "IO12_P18") (pintype "bidirectional"))
    )
    (net (code "20") (name "Net-(U3-IO13)") (class "Default")
      (node (ref "U1") (pin "B22") (pinfunction "22_B22") (pintype "bidirectional"))
      (node (ref "U1") (pin "N22") (pinfunction "22_N22") (pintype "bidirectional"))
      (node (ref "U1") (pin "O22") (pinfunction "22_O22") (pintype "bidirectional"))
      (node (ref "U1") (pin "P22") (pinfunction "22_P22") (pintype "bidirectional"))
      (node (ref "U1") (pin "Q22") (pinfunction "22_Q22") (pintype "bidirectional"))
      (node (ref "U1") (pin "T22") (pinfunction "22_T22") (pintype "bidirectional"))
      (node (ref "U2") (pin "B22") (pinfunction "22_B22") (pintype "bidirectional"))
      (node (ref "U2") (pin "N22") (pinfunction "22_N22") (pintype "bidirectional"))
      (node (ref "U2") (pin "O22") (pinfunction "22_O22") (pintype "bidirectional"))
      (node (ref "U2") (pin "P22") (pinfunction "22_P22") (pintype "bidirectional"))
      (node (ref "U2") (pin "Q22") (pinfunction "22_Q22") (pintype "bidirectional"))
      (node (ref "U2") (pin "T22") (pinfunction "22_T22") (pintype "bidirectional"))
      (node (ref "U3") (pin "P22") (pinfunction "IO13_P22") (pintype "bidirectional"))
      (node (ref "U4") (pin "P22") (pinfunction "IO13_P22") (pintype "bidirectional"))
      (node (ref "U5") (pin "P22") (pinfunction "IO13_P22") (pintype "bidirectional"))
    )
    (net (code "21") (name "Net-(U3-IO14)") (class "Default")
      (node (ref "U1") (pin "B23") (pinfunction "23_B23") (pintype "bidirectional"))
      (node (ref "U1") (pin "N23") (pinfunction "23_N23") (pintype "bidirectional"))
      (node (ref "U1") (pin "O23") (pinfunction "23_O23") (pintype "bidirectional"))
      (node (ref "U1") (pin "P23") (pinfunction "23_P23") (pintype "bidirectional"))
      (node (ref "U1") (pin "Q23") (pinfunction "23_Q23") (pintype "bidirectional"))
      (node (ref "U1") (pin "T23") (pinfunction "23_T23") (pintype "bidirectional"))
      (node (ref "U2") (pin "B23") (pinfunction "23_B23") (pintype "bidirectional"))
      (node (ref "U2") (pin "N23") (pinfunction "23_N23") (pintype "bidirectional"))
      (node (ref "U2") (pin "O23") (pinfunction "23_O23") (pintype "bidirectional"))
      (node (ref "U2") (pin "P23") (pinfunction "23_P23") (pintype "bidirectional"))
      (node (ref "U2") (pin "Q23") (pinfunction "23_Q23") (pintype "bidirectional"))
      (node (ref "U2") (pin "T23") (pinfunction "23_T23") (pintype "bidirectional"))
      (node (ref "U3") (pin "P23") (pinfunction "IO14_P23") (pintype "bidirectional"))
      (node (ref "U4") (pin "P23") (pinfunction "IO14_P23") (pintype "bidirectional"))
      (node (ref "U5") (pin "P23") (pinfunction "IO14_P23") (pintype "bidirectional"))
    )
    (net (code "22") (name "Net-(U3-IO15)") (class "Default")
      (node (ref "U1") (pin "B7") (pinfunction "7_B7") (pintype "bidirectional"))
      (node (ref "U1") (pin "N7") (pinfunction "7_N7") (pintype "bidirectional"))
      (node (ref "U1") (pin "O7") (pinfunction "7_O7") (pintype "bidirectional"))
      (node (ref "U1") (pin "P7") (pinfunction "7_P7") (pintype "bidirectional"))
      (node (ref "U1") (pin "Q7") (pinfunction "7_Q7") (pintype "bidirectional"))
      (node (ref "U1") (pin "T7") (pinfunction "7_T7") (pintype "bidirectional"))
      (node (ref "U2") (pin "B7") (pinfunction "7_B7") (pintype "bidirectional"))
      (node (ref "U2") (pin "N7") (pinfunction "7_N7") (pintype "bidirectional"))
      (node (ref "U2") (pin "O7") (pinfunction "7_O7") (pintype "bidirectional"))
      (node (ref "U2") (pin "P7") (pinfunction "7_P7") (pintype "bidirectional"))
      (node (ref "U2") (pin "Q7") (pinfunction "7_Q7") (pintype "bidirectional"))
      (node (ref "U2") (pin "T7") (pinfunction "7_T7") (pintype "bidirectional"))
      (node (ref "U3") (pin "P7") (pinfunction "IO15_P7") (pintype "bidirectional"))
      (node (ref "U4") (pin "P7") (pinfunction "IO15_P7") (pintype "bidirectional"))
      (node (ref "U5") (pin "P7") (pinfunction "IO15_P7") (pintype "bidirectional"))
    )
    (net (code "23") (name "Net-(U3-IO16)") (class "Default")
      (node (ref "U1") (pin "B8") (pinfunction "8_B8") (pintype "bidirectional"))
      (node (ref "U1") (pin "N8") (pinfunction "8_N8") (pintype "bidirectional"))
      (node (ref "U1") (pin "O8") (pinfunction "8_O8") (pintype "bidirectional"))
      (node (ref "U1") (pin "P8") (pinfunction "8_P8") (pintype "bidirectional"))
      (node (ref "U1") (pin "Q8") (pinfunction "8_Q8") (pintype "bidirectional"))
      (node (ref "U1") (pin "T8") (pinfunction "8_T8") (pintype "bidirectional"))
      (node (ref "U2") (pin "B8") (pinfunction "8_B8") (pintype "bidirectional"))
      (node (ref "U2") (pin "N8") (pinfunction "8_N8") (pintype "bidirectional"))
      (node (ref "U2") (pin "O8") (pinfunction "8_O8") (pintype "bidirectional"))
      (node (ref "U2") (pin "P8") (pinfunction "8_P8") (pintype "bidirectional"))
      (node (ref "U2") (pin "Q8") (pinfunction "8_Q8") (pintype "bidirectional"))
      (node (ref "U2") (pin "T8") (pinfunction "8_T8") (pintype "bidirectional"))
      (node (ref "U3") (pin "P8") (pinfunction "IO16_P8") (pintype "bidirectional"))
      (node (ref "U4") (pin "P8") (pinfunction "IO16_P8") (pintype "bidirectional"))
      (node (ref "U5") (pin "P8") (pinfunction "IO16_P8") (pintype "bidirectional"))
    )
    (net (code "24") (name "Net-(U3-IO17)") (class "Default")
      (node (ref "U1") (pin "B9") (pinfunction "9_B9") (pintype "bidirectional"))
      (node (ref "U1") (pin "N9") (pinfunction "9_N9") (pintype "bidirectional"))
      (node (ref "U1") (pin "O9") (pinfunction "9_O9") (pintype "bidirectional"))
      (node (ref "U1") (pin "P9") (pinfunction "9_P9") (pintype "bidirectional"))
      (node (ref "U1") (pin "Q9") (pinfunction "9_Q9") (pintype "bidirectional"))
      (node (ref "U1") (pin "T9") (pinfunction "9_T9") (pintype "bidirectional"))
      (node (ref "U2") (pin "B9") (pinfunction "9_B9") (pintype "bidirectional"))
      (node (ref "U2") (pin "N9") (pinfunction "9_N9") (pintype "bidirectional"))
      (node (ref "U2") (pin "O9") (pinfunction "9_O9") (pintype "bidirectional"))
      (node (ref "U2") (pin "P9") (pinfunction "9_P9") (pintype "bidirectional"))
      (node (ref "U2") (pin "Q9") (pinfunction "9_Q9") (pintype "bidirectional"))
      (node (ref "U2") (pin "T9") (pinfunction "9_T9") (pintype "bidirectional"))
      (node (ref "U3") (pin "P9") (pinfunction "IO17_P9") (pintype "bidirectional"))
      (node (ref "U4") (pin "P9") (pinfunction "IO17_P9") (pintype "bidirectional"))
      (node (ref "U5") (pin "P9") (pinfunction "IO17_P9") (pintype "bidirectional"))
    )
    (net (code "25") (name "Net-(U3-IO18)") (class "Default")
      (node (ref "U1") (pin "B10") (pinfunction "10_B10") (pintype "bidirectional"))
      (node (ref "U1") (pin "N10") (pinfunction "10_N10") (pintype "bidirectional"))
      (node (ref "U1") (pin "O10") (pinfunction "10_O10") (pintype "bidirectional"))
      (node (ref "U1") (pin "P10") (pinfunction "10_P10") (pintype "bidirectional"))
      (node (ref "U1") (pin "Q10") (pinfunction "10_Q10") (pintype "bidirectional"))
      (node (ref "U1") (pin "T10") (pinfunction "10_T10") (pintype "bidirectional"))
      (node (ref "U2") (pin "B10") (pinfunction "10_B10") (pintype "bidirectional"))
      (node (ref "U2") (pin "N10") (pinfunction "10_N10") (pintype "bidirectional"))
      (node (ref "U2") (pin "O10") (pinfunction "10_O10") (pintype "bidirectional"))
      (node (ref "U2") (pin "P10") (pinfunction "10_P10") (pintype "bidirectional"))
      (node (ref "U2") (pin "Q10") (pinfunction "10_Q10") (pintype "bidirectional"))
      (node (ref "U2") (pin "T10") (pinfunction "10_T10") (pintype "bidirectional"))
      (node (ref "U3") (pin "P10") (pinfunction "IO18_P10") (pintype "bidirectional"))
      (node (ref "U4") (pin "P10") (pinfunction "IO18_P10") (pintype "bidirectional"))
      (node (ref "U5") (pin "P10") (pinfunction "IO18_P10") (pintype "bidirectional"))
    )
    (net (code "26") (name "Net-(U3-IO19)") (class "Default")
      (node (ref "U1") (pin "B12") (pinfunction "12_B12") (pintype "bidirectional"))
      (node (ref "U1") (pin "N12") (pinfunction "12_N12") (pintype "bidirectional"))
      (node (ref "U1") (pin "O12") (pinfunction "12_O12") (pintype "bidirectional"))
      (node (ref "U1") (pin "P12") (pinfunction "12_P12") (pintype "bidirectional"))
      (node (ref "U1") (pin "Q12") (pinfunction "12_Q12") (pintype "bidirectional"))
      (node (ref "U1") (pin "T12") (pinfunction "12_T12") (pintype "bidirectional"))
      (node (ref "U2") (pin "B12") (pinfunction "12_B12") (pintype "bidirectional"))
      (node (ref "U2") (pin "N12") (pinfunction "12_N12") (pintype "bidirectional"))
      (node (ref "U2") (pin "O12") (pinfunction "12_O12") (pintype "bidirectional"))
      (node (ref "U2") (pin "P12") (pinfunction "12_P12") (pintype "bidirectional"))
      (node (ref "U2") (pin "Q12") (pinfunction "12_Q12") (pintype "bidirectional"))
      (node (ref "U2") (pin "T12") (pinfunction "12_T12") (pintype "bidirectional"))
      (node (ref "U3") (pin "P12") (pinfunction "IO19_P12") (pintype "bidirectional"))
      (node (ref "U4") (pin "P12") (pinfunction "IO19_P12") (pintype "bidirectional"))
      (node (ref "U5") (pin "P12") (pinfunction "IO19_P12") (pintype "bidirectional"))
    )
    (net (code "27") (name "Net-(U3-IO20)") (class "Default")
      (node (ref "U1") (pin "B13") (pinfunction "13_B13") (pintype "bidirectional"))
      (node (ref "U1") (pin "N13") (pinfunction "13_N13") (pintype "bidirectional"))
      (node (ref "U1") (pin "O13") (pinfunction "13_O13") (pintype "bidirectional"))
      (node (ref "U1") (pin "P13") (pinfunction "13_P13") (pintype "bidirectional"))
      (node (ref "U1") (pin "Q13") (pinfunction "13_Q13") (pintype "bidirectional"))
      (node (ref "U1") (pin "T13") (pinfunction "13_T13") (pintype "bidirectional"))
      (node (ref "U2") (pin "B13") (pinfunction "13_B13") (pintype "bidirectional"))
      (node (ref "U2") (pin "N13") (pinfunction "13_N13") (pintype "bidirectional"))
      (node (ref "U2") (pin "O13") (pinfunction "13_O13") (pintype "bidirectional"))
      (node (ref "U2") (pin "P13") (pinfunction "13_P13") (pintype "bidirectional"))
      (node (ref "U2") (pin "Q13") (pinfunction "13_Q13") (pintype "bidirectional"))
      (node (ref "U2") (pin "T13") (pinfunction "13_T13") (pintype "bidirectional"))
      (node (ref "U3") (pin "P13") (pinfunction "IO20_P13") (pintype "bidirectional"))
      (node (ref "U4") (pin "P13") (pinfunction "IO20_P13") (pintype "bidirectional"))
      (node (ref "U5") (pin "P13") (pinfunction "IO20_P13") (pintype "bidirectional"))
    )
    (net (code "28") (name "Net-(U3-IO21)") (class "Default")
      (node (ref "U1") (pin "B24") (pinfunction "24_B24") (pintype "bidirectional"))
      (node (ref "U1") (pin "N24") (pinfunction "24_N24") (pintype "bidirectional"))
      (node (ref "U1") (pin "O24") (pinfunction "24_O24") (pintype "bidirectional"))
      (node (ref "U1") (pin "P24") (pinfunction "24_P24") (pintype "bidirectional"))
      (node (ref "U1") (pin "Q24") (pinfunction "24_Q24") (pintype "bidirectional"))
      (node (ref "U1") (pin "T24") (pinfunction "24_T24") (pintype "bidirectional"))
      (node (ref "U2") (pin "B24") (pinfunction "24_B24") (pintype "bidirectional"))
      (node (ref "U2") (pin "N24") (pinfunction "24_N24") (pintype "bidirectional"))
      (node (ref "U2") (pin "O24") (pinfunction "24_O24") (pintype "bidirectional"))
      (node (ref "U2") (pin "P24") (pinfunction "24_P24") (pintype "bidirectional"))
      (node (ref "U2") (pin "Q24") (pinfunction "24_Q24") (pintype "bidirectional"))
      (node (ref "U2") (pin "T24") (pinfunction "24_T24") (pintype "bidirectional"))
      (node (ref "U3") (pin "P24") (pinfunction "IO21_P24") (pintype "bidirectional"))
      (node (ref "U4") (pin "P24") (pinfunction "IO21_P24") (pintype "bidirectional"))
      (node (ref "U5") (pin "P24") (pinfunction "IO21_P24") (pintype "bidirectional"))
    )
    (net (code "29") (name "Net-(U3-IO35)") (class "Default")
      (node (ref "U1") (pin "B28") (pinfunction "28_B28") (pintype "bidirectional"))
      (node (ref "U1") (pin "N28") (pinfunction "28_N28") (pintype "bidirectional"))
      (node (ref "U1") (pin "O28") (pinfunction "28_O28") (pintype "bidirectional"))
      (node (ref "U1") (pin "P28") (pinfunction "28_P28") (pintype "bidirectional"))
      (node (ref "U1") (pin "Q28") (pinfunction "28_Q28") (pintype "bidirectional"))
      (node (ref "U1") (pin "T28") (pinfunction "28_T28") (pintype "bidirectional"))
      (node (ref "U2") (pin "B28") (pinfunction "28_B28") (pintype "bidirectional"))
      (node (ref "U2") (pin "N28") (pinfunction "28_N28") (pintype "bidirectional"))
      (node (ref "U2") (pin "O28") (pinfunction "28_O28") (pintype "bidirectional"))
      (node (ref "U2") (pin "P28") (pinfunction "28_P28") (pintype "bidirectional"))
      (node (ref "U2") (pin "Q28") (pinfunction "28_Q28") (pintype "bidirectional"))
      (node (ref "U2") (pin "T28") (pinfunction "28_T28") (pintype "bidirectional"))
      (node (ref "U3") (pin "P28") (pinfunction "IO35_P28") (pintype "bidirectional"))
      (node (ref "U4") (pin "P28") (pinfunction "IO35_P28") (pintype "bidirectional"))
      (node (ref "U5") (pin "P28") (pinfunction "IO35_P28") (pintype "bidirectional"))
    )
    (net (code "30") (name "Net-(U3-IO36)") (class "Default")
      (node (ref "U1") (pin "B29") (pinfunction "29_B29") (pintype "bidirectional"))
      (node (ref "U1") (pin "N29") (pinfunction "29_N29") (pintype "bidirectional"))
      (node (ref "U1") (pin "O29") (pinfunction "29_O29") (pintype "bidirectional"))
      (node (ref "U1") (pin "P29") (pinfunction "29_P29") (pintype "bidirectional"))
      (node (ref "U1") (pin "Q29") (pinfunction "29_Q29") (pintype "bidirectional"))
      (node (ref "U1") (pin "T29") (pinfunction "29_T29") (pintype "bidirectional"))
      (node (ref "U2") (pin "B29") (pinfunction "29_B29") (pintype "bidirectional"))
      (node (ref "U2") (pin "N29") (pinfunction "29_N29") (pintype "bidirectional"))
      (node (ref "U2") (pin "O29") (pinfunction "29_O29") (pintype "bidirectional"))
      (node (ref "U2") (pin "P29") (pinfunction "29_P29") (pintype "bidirectional"))
      (node (ref "U2") (pin "Q29") (pinfunction "29_Q29") (pintype "bidirectional"))
      (node (ref "U2") (pin "T29") (pinfunction "29_T29") (pintype "bidirectional"))
      (node (ref "U3") (pin "P29") (pinfunction "IO36_P29") (pintype "bidirectional"))
      (node (ref "U4") (pin "P29") (pinfunction "IO36_P29") (pintype "bidirectional"))
      (node (ref "U5") (pin "P29") (pinfunction "IO36_P29") (pintype "bidirectional"))
    )
    (net (code "31") (name "Net-(U3-IO37)") (class "Default")
      (node (ref "U1") (pin "B30") (pinfunction "30_B30") (pintype "bidirectional"))
      (node (ref "U1") (pin "N30") (pinfunction "30_N30") (pintype "bidirectional"))
      (node (ref "U1") (pin "O30") (pinfunction "30_O30") (pintype "bidirectional"))
      (node (ref "U1") (pin "P30") (pinfunction "30_P30") (pintype "bidirectional"))
      (node (ref "U1") (pin "Q30") (pinfunction "30_Q30") (pintype "bidirectional"))
      (node (ref "U1") (pin "T30") (pinfunction "30_T30") (pintype "bidirectional"))
      (node (ref "U2") (pin "B30") (pinfunction "30_B30") (pintype "bidirectional"))
      (node (ref "U2") (pin "N30") (pinfunction "30_N30") (pintype "bidirectional"))
      (node (ref "U2") (pin "O30") (pinfunction "30_O30") (pintype "bidirectional"))
      (node (ref "U2") (pin "P30") (pinfunction "30_P30") (pintype "bidirectional"))
      (node (ref "U2") (pin "Q30") (pinfunction "30_Q30") (pintype "bidirectional"))
      (node (ref "U2") (pin "T30") (pinfunction "30_T30") (pintype "bidirectional"))
      (node (ref "U3") (pin "P30") (pinfunction "IO37_P30") (pintype "bidirectional"))
      (node (ref "U4") (pin "P30") (pinfunction "IO37_P30") (pintype "bidirectional"))
      (node (ref "U5") (pin "P30") (pinfunction "IO37_P30") (pintype "bidirectional"))
    )
    (net (code "32") (name "Net-(U3-IO38)") (class "Default")
      (node (ref "U1") (pin "B31") (pinfunction "31_B31") (pintype "bidirectional"))
      (node (ref "U1") (pin "N31") (pinfunction "31_N31") (pintype "bidirectional"))
      (node (ref "U1") (pin "O31") (pinfunction "31_O31") (pintype "bidirectional"))
      (node (ref "U1") (pin "P31") (pinfunction "31_P31") (pintype "bidirectional"))
      (node (ref "U1") (pin "Q31") (pinfunction "31_Q31") (pintype "bidirectional"))
      (node (ref "U1") (pin "T31") (pinfunction "31_T31") (pintype "bidirectional"))
      (node (ref "U2") (pin "B31") (pinfunction "31_B31") (pintype "bidirectional"))
      (node (ref "U2") (pin "N31") (pinfunction "31_N31") (pintype "bidirectional"))
      (node (ref "U2") (pin "O31") (pinfunction "31_O31") (pintype "bidirectional"))
      (node (ref "U2") (pin "P31") (pinfunction "31_P31") (pintype "bidirectional"))
      (node (ref "U2") (pin "Q31") (pinfunction "31_Q31") (pintype "bidirectional"))
      (node (ref "U2") (pin "T31") (pinfunction "31_T31") (pintype "bidirectional"))
      (node (ref "U3") (pin "P31") (pinfunction "IO38_P31") (pintype "bidirectional"))
      (node (ref "U4") (pin "P31") (pinfunction "IO38_P31") (pintype "bidirectional"))
      (node (ref "U5") (pin "P31") (pinfunction "IO38_P31") (pintype "bidirectional"))
    )
    (net (code "33") (name "Net-(U3-IO39)") (class "Default")
      (node (ref "U1") (pin "B32") (pinfunction "32_B32") (pintype "bidirectional"))
      (node (ref "U1") (pin "N32") (pinfunction "32_N32") (pintype "bidirectional"))
      (node (ref "U1") (pin "O32") (pinfunction "32_O32") (pintype "bidirectional"))
      (node (ref "U1") (pin "P32") (pinfunction "32_P32") (pintype "bidirectional"))
      (node (ref "U1") (pin "Q32") (pinfunction "32_Q32") (pintype "bidirectional"))
      (node (ref "U1") (pin "T32") (pinfunction "32_T32") (pintype "bidirectional"))
      (node (ref "U2") (pin "B32") (pinfunction "32_B32") (pintype "bidirectional"))
      (node (ref "U2") (pin "N32") (pinfunction "32_N32") (pintype "bidirectional"))
      (node (ref "U2") (pin "O32") (pinfunction "32_O32") (pintype "bidirectional"))
      (node (ref "U2") (pin "P32") (pinfunction "32_P32") (pintype "bidirectional"))
      (node (ref "U2") (pin "Q32") (pinfunction "32_Q32") (pintype "bidirectional"))
      (node (ref "U2") (pin "T32") (pinfunction "32_T32") (pintype "bidirectional"))
      (node (ref "U3") (pin "P32") (pinfunction "IO39_P32") (pintype "bidirectional"))
      (node (ref "U4") (pin "P32") (pinfunction "IO39_P32") (pintype "bidirectional"))
      (node (ref "U5") (pin "P32") (pinfunction "IO39_P32") (pintype "bidirectional"))
    )
    (net (code "34") (name "Net-(U3-IO40)") (class "Default")
      (node (ref "U1") (pin "B33") (pinfunction "33_B33") (pintype "bidirectional"))
      (node (ref "U1") (pin "N33") (pinfunction "33_N33") (pintype "bidirectional"))
      (node (ref "U1") (pin "O33") (pinfunction "33_O33") (pintype "bidirectional"))
      (node (ref "U1") (pin "P33") (pinfunction "33_P33") (pintype "bidirectional"))
      (node (ref "U1") (pin "Q33") (pinfunction "33_Q33") (pintype "bidirectional"))
      (node (ref "U1") (pin "T33") (pinfunction "33_T33") (pintype "bidirectional"))
      (node (ref "U2") (pin "B33") (pinfunction "33_B33") (pintype "bidirectional"))
      (node (ref "U2") (pin "N33") (pinfunction "33_N33") (pintype "bidirectional"))
      (node (ref "U2") (pin "O33") (pinfunction "33_O33") (pintype "bidirectional"))
      (node (ref "U2") (pin "P33") (pinfunction "33_P33") (pintype "bidirectional"))
      (node (ref "U2") (pin "Q33") (pinfunction "33_Q33") (pintype "bidirectional"))
      (node (ref "U2") (pin "T33") (pinfunction "33_T33") (pintype "bidirectional"))
      (node (ref "U3") (pin "P33") (pinfunction "IO40_P33") (pintype "bidirectional"))
      (node (ref "U4") (pin "P33") (pinfunction "IO40_P33") (pintype "bidirectional"))
      (node (ref "U5") (pin "P33") (pinfunction "IO40_P33") (pintype "bidirectional"))
    )
    (net (code "35") (name "Net-(U3-IO41)") (class "Default")
      (node (ref "U1") (pin "B34") (pinfunction "34_B34") (pintype "bidirectional"))
      (node (ref "U1") (pin "N34") (pinfunction "34_N34") (pintype "bidirectional"))
      (node (ref "U1") (pin "O34") (pinfunction "34_O34") (pintype "bidirectional"))
      (node (ref "U1") (pin "P34") (pinfunction "34_P34") (pintype "bidirectional"))
      (node (ref "U1") (pin "Q34") (pinfunction "34_Q34") (pintype "bidirectional"))
      (node (ref "U1") (pin "T34") (pinfunction "34_T34") (pintype "bidirectional"))
      (node (ref "U2") (pin "B34") (pinfunction "34_B34") (pintype "bidirectional"))
      (node (ref "U2") (pin "N34") (pinfunction "34_N34") (pintype "bidirectional"))
      (node (ref "U2") (pin "O34") (pinfunction "34_O34") (pintype "bidirectional"))
      (node (ref "U2") (pin "P34") (pinfunction "34_P34") (pintype "bidirectional"))
      (node (ref "U2") (pin "Q34") (pinfunction "34_Q34") (pintype "bidirectional"))
      (node (ref "U2") (pin "T34") (pinfunction "34_T34") (pintype "bidirectional"))
      (node (ref "U3") (pin "P34") (pinfunction "IO41_P34") (pintype "bidirectional"))
      (node (ref "U4") (pin "P34") (pinfunction "IO41_P34") (pintype "bidirectional"))
      (node (ref "U5") (pin "P34") (pinfunction "IO41_P34") (pintype "bidirectional"))
    )
    (net (code "36") (name "Net-(U3-IO42)") (class "Default")
      (node (ref "U1") (pin "B35") (pinfunction "35_B35") (pintype "bidirectional"))
      (node (ref "U1") (pin "N35") (pinfunction "35_N35") (pintype "bidirectional"))
      (node (ref "U1") (pin "O35") (pinfunction "35_O35") (pintype "bidirectional"))
      (node (ref "U1") (pin "P35") (pinfunction "35_P35") (pintype "bidirectional"))
      (node (ref "U1") (pin "Q35") (pinfunction "35_Q35") (pintype "bidirectional"))
      (node (ref "U1") (pin "T35") (pinfunction "35_T35") (pintype "bidirectional"))
      (node (ref "U2") (pin "B35") (pinfunction "35_B35") (pintype "bidirectional"))
      (node (ref "U2") (pin "N35") (pinfunction "35_N35") (pintype "bidirectional"))
      (node (ref "U2") (pin "O35") (pinfunction "35_O35") (pintype "bidirectional"))
      (node (ref "U2") (pin "P35") (pinfunction "35_P35") (pintype "bidirectional"))
      (node (ref "U2") (pin "Q35") (pinfunction "35_Q35") (pintype "bidirectional"))
      (node (ref "U2") (pin "T35") (pinfunction "35_T35") (pintype "bidirectional"))
      (node (ref "U3") (pin "P35") (pinfunction "IO42_P35") (pintype "bidirectional"))
      (node (ref "U4") (pin "P35") (pinfunction "IO42_P35") (pintype "bidirectional"))
      (node (ref "U5") (pin "P35") (pinfunction "IO42_P35") (pintype "bidirectional"))
    )
    (net (code "37") (name "Net-(U3-IO47)") (class "Default")
      (node (ref "U1") (pin "B25") (pinfunction "25_B25") (pintype "bidirectional"))
      (node (ref "U1") (pin "N25") (pinfunction "25_N25") (pintype "bidirectional"))
      (node (ref "U1") (pin "O25") (pinfunction "25_O25") (pintype "bidirectional"))
      (node (ref "U1") (pin "P25") (pinfunction "25_P25") (pintype "bidirectional"))
      (node (ref "U1") (pin "Q25") (pinfunction "25_Q25") (pintype "bidirectional"))
      (node (ref "U1") (pin "T25") (pinfunction "25_T25") (pintype "bidirectional"))
      (node (ref "U2") (pin "B25") (pinfunction "25_B25") (pintype "bidirectional"))
      (node (ref "U2") (pin "N25") (pinfunction "25_N25") (pintype "bidirectional"))
      (node (ref "U2") (pin "O25") (pinfunction "25_O25") (pintype "bidirectional"))
      (node (ref "U2") (pin "P25") (pinfunction "25_P25") (pintype "bidirectional"))
      (node (ref "U2") (pin "Q25") (pinfunction "25_Q25") (pintype "bidirectional"))
      (node (ref "U2") (pin "T25") (pinfunction "25_T25") (pintype "bidirectional"))
      (node (ref "U3") (pin "P25") (pinfunction "IO47_P25") (pintype "bidirectional"))
      (node (ref "U4") (pin "P25") (pinfunction "IO47_P25") (pintype "bidirectional"))
      (node (ref "U5") (pin "P25") (pinfunction "IO47_P25") (pintype "bidirectional"))
    )
    (net (code "38") (name "Net-(U3-IO48)") (class "Default")
      (node (ref "U1") (pin "B26") (pinfunction "26_B26") (pintype "bidirectional"))
      (node (ref "U1") (pin "N26") (pinfunction "26_N26") (pintype "bidirectional"))
      (node (ref "U1") (pin "O26") (pinfunction "26_O26") (pintype "bidirectional"))
      (node (ref "U1") (pin "P26") (pinfunction "26_P26") (pintype "bidirectional"))
      (node (ref "U1") (pin "Q26") (pinfunction "26_Q26") (pintype "bidirectional"))
      (node (ref "U1") (pin "T26") (pinfunction "26_T26") (pintype "bidirectional"))
      (node (ref "U2") (pin "B26") (pinfunction "26_B26") (pintype "bidirectional"))
      (node (ref "U2") (pin "N26") (pinfunction "26_N26") (pintype "bidirectional"))
      (node (ref "U2") (pin "O26") (pinfunction "26_O26") (pintype "bidirectional"))
      (node (ref "U2") (pin "P26") (pinfunction "26_P26") (pintype "bidirectional"))
      (node (ref "U2") (pin "Q26") (pinfunction "26_Q26") (pintype "bidirectional"))
      (node (ref "U2") (pin "T26") (pinfunction "26_T26") (pintype "bidirectional"))
      (node (ref "U3") (pin "P26") (pinfunction "IO48_P26") (pintype "bidirectional"))
      (node (ref "U4") (pin "P26") (pinfunction "IO48_P26") (pintype "bidirectional"))
      (node (ref "U5") (pin "P26") (pinfunction "IO48_P26") (pintype "bidirectional"))
    )
    (net (code "39") (name "Net-(U3-RXD)") (class "Default")
      (node (ref "U1") (pin "B36") (pinfunction "36_B36") (pintype "bidirectional"))
      (node (ref "U1") (pin "N36") (pinfunction "36_N36") (pintype "bidirectional"))
      (node (ref "U1") (pin "O36") (pinfunction "36_O36") (pintype "bidirectional"))
      (node (ref "U1") (pin "P36") (pinfunction "36_P36") (pintype "bidirectional"))
      (node (ref "U1") (pin "Q36") (pinfunction "36_Q36") (pintype "bidirectional"))
      (node (ref "U1") (pin "T36") (pinfunction "36_T36") (pintype "bidirectional"))
      (node (ref "U2") (pin "B36") (pinfunction "36_B36") (pintype "bidirectional"))
      (node (ref "U2") (pin "N36") (pinfunction "36_N36") (pintype "bidirectional"))
      (node (ref "U2") (pin "O36") (pinfunction "36_O36") (pintype "bidirectional"))
      (node (ref "U2") (pin "P36") (pinfunction "36_P36") (pintype "bidirectional"))
      (node (ref "U2") (pin "Q36") (pinfunction "36_Q36") (pintype "bidirectional"))
      (node (ref "U2") (pin "T36") (pinfunction "36_T36") (pintype "bidirectional"))
      (node (ref "U3") (pin "P36") (pinfunction "RXD_P36") (pintype "bidirectional"))
      (node (ref "U4") (pin "P36") (pinfunction "RXD_P36") (pintype "bidirectional"))
      (node (ref "U5") (pin "P36") (pinfunction "RXD_P36") (pintype "bidirectional"))
    )
    (net (code "40") (name "Net-(U3-TXD)") (class "Default")
      (node (ref "U1") (pin "B37") (pinfunction "37_B37") (pintype "bidirectional"))
      (node (ref "U1") (pin "N37") (pinfunction "37_N37") (pintype "bidirectional"))
      (node (ref "U1") (pin "O37") (pinfunction "37_O37") (pintype "bidirectional"))
      (node (ref "U1") (pin "P37") (pinfunction "37_P37") (pintype "bidirectional"))
      (node (ref "U1") (pin "Q37") (pinfunction "37_Q37") (pintype "bidirectional"))
      (node (ref "U1") (pin "T37") (pinfunction "37_T37") (pintype "bidirectional"))
      (node (ref "U2") (pin "B37") (pinfunction "37_B37") (pintype "bidirectional"))
      (node (ref "U2") (pin "N37") (pinfunction "37_N37") (pintype "bidirectional"))
      (node (ref "U2") (pin "O37") (pinfunction "37_O37") (pintype "bidirectional"))
      (node (ref "U2") (pin "P37") (pinfunction "37_P37") (pintype "bidirectional"))
      (node (ref "U2") (pin "Q37") (pinfunction "37_Q37") (pintype "bidirectional"))
      (node (ref "U2") (pin "T37") (pinfunction "37_T37") (pintype "bidirectional"))
      (node (ref "U3") (pin "P37") (pinfunction "TXD_P37") (pintype "bidirectional"))
      (node (ref "U4") (pin "P37") (pinfunction "TXD_P37") (pintype "bidirectional"))
      (node (ref "U5") (pin "P37") (pinfunction "TXD_P37") (pintype "bidirectional"))
    )
    (net (code "41") (name "Net-(X1-PadP1)") (class "Default")
      (node (ref "X1") (pin "P1") (pinfunction "P1_P1") (pintype "bidirectional"))
      (node (ref "X2") (pin "P1") (pinfunction "P1_P1") (pintype "bidirectional"))
      (node (ref "X3") (pin "P1") (pinfunction "P1_P1") (pintype "bidirectional"))
    )
    (net (code "42") (name "Net-(X1-PadP2)") (class "Default")
      (node (ref "X1") (pin "P2") (pinfunction "P2_P2") (pintype "bidirectional"))
      (node (ref "X2") (pin "P2") (pinfunction "P2_P2") (pintype "bidirectional"))
      (node (ref "X3") (pin "P2") (pinfunction "P2_P2") (pintype "bidirectional"))
    )
    (net (code "43") (name "Net-(X1-PadP3)") (class "Default")
      (node (ref "X1") (pin "P3") (pinfunction "P3_P3") (pintype "bidirectional"))
      (node (ref "X2") (pin "P3") (pinfunction "P3_P3") (pintype "bidirectional"))
      (node (ref "X3") (pin "P3") (pinfunction "P3_P3") (pintype "bidirectional"))
    )
    (net (code "44") (name "Net-(X1-PadP4)") (class "Default")
      (node (ref "X1") (pin "P4") (pinfunction "P4_P4") (pintype "bidirectional"))
      (node (ref "X2") (pin "P4") (pinfunction "P4_P4") (pintype "bidirectional"))
      (node (ref "X3") (pin "P4") (pinfunction "P4_P4") (pintype "bidirectional"))
    )
    (net (code "45") (name "Net-(X1-PadP5)") (class "Default")
      (node (ref "X1") (pin "P5") (pinfunction "P5_P5") (pintype "bidirectional"))
      (node (ref "X2") (pin "P5") (pinfunction "P5_P5") (pintype "bidirectional"))
      (node (ref "X3") (pin "P5") (pinfunction "P5_P5") (pintype "bidirectional"))
    )
    (net (code "46") (name "Net-(X1-PadP6)") (class "Default")
      (node (ref "X1") (pin "P6") (pinfunction "P6_P6") (pintype "bidirectional"))
      (node (ref "X2") (pin "P6") (pinfunction "P6_P6") (pintype "bidirectional"))
      (node (ref "X3") (pin "P6") (pinfunction "P6_P6") (pintype "bidirectional"))
    )
    (net (code "47") (name "Net-(X1-PadP7)") (class "Default")
      (node (ref "X1") (pin "P7") (pinfunction "P7_P7") (pintype "bidirectional"))
      (node (ref "X2") (pin "P7") (pinfunction "P7_P7") (pintype "bidirectional"))
      (node (ref "X3") (pin "P7") (pinfunction "P7_P7") (pintype "bidirectional"))
    )
    (net (code "48") (name "Net-(X1-PadP8)") (class "Default")
      (node (ref "X1") (pin "P8") (pinfunction "P8_P8") (pintype "bidirectional"))
      (node (ref "X2") (pin "P8") (pinfunction "P8_P8") (pintype "bidirectional"))
      (node (ref "X3") (pin "P8") (pinfunction "P8_P8") (pintype "bidirectional"))
    )
    (net (code "49") (name "Net-(X1-PadP9)") (class "Default")
      (node (ref "X1") (pin "P9") (pinfunction "P9_P9") (pintype "bidirectional"))
      (node (ref "X2") (pin "P9") (pinfunction "P9_P9") (pintype "bidirectional"))
      (node (ref "X3") (pin "P9") (pinfunction "P9_P9") (pintype "bidirectional"))
    )
    (net (code "50") (name "Net-(X1-PadP10)") (class "Default")
      (node (ref "X1") (pin "P10") (pinfunction "P10_P10") (pintype "bidirectional"))
      (node (ref "X2") (pin "P10") (pinfunction "P10_P10") (pintype "bidirectional"))
      (node (ref "X3") (pin "P10") (pinfunction "P10_P10") (pintype "bidirectional"))
    )
    (net (code "51") (name "Net-(X1-PadP11)") (class "Default")
      (node (ref "X1") (pin "P11") (pinfunction "P11_P11") (pintype "bidirectional"))
      (node (ref "X2") (pin "P11") (pinfunction "P11_P11") (pintype "bidirectional"))
      (node (ref "X3") (pin "P11") (pinfunction "P11_P11") (pintype "bidirectional"))
    )
    (net (code "52") (name "Net-(X1-PadP12)") (class "Default")
      (node (ref "X1") (pin "P12") (pinfunction "P12_P12") (pintype "bidirectional"))
      (node (ref "X2") (pin "P12") (pinfunction "P12_P12") (pintype "bidirectional"))
      (node (ref "X3") (pin "P12") (pinfunction "P12_P12") (pintype "bidirectional"))
    )
    (net (code "53") (name "Net-(X1-PadP13)") (class "Default")
      (node (ref "X1") (pin "P13") (pinfunction "P13_P13") (pintype "bidirectional"))
      (node (ref "X2") (pin "P13") (pinfunction "P13_P13") (pintype "bidirectional"))
      (node (ref "X3") (pin "P13") (pinfunction "P13_P13") (pintype "bidirectional"))
    )
    (net (code "54") (name "Net-(X4-PadP1)") (class "Default")
      (node (ref "X4") (pin "P1") (pinfunction "P1_P1") (pintype "bidirectional"))
      (node (ref "X5") (pin "P1") (pinfunction "P1_P1") (pintype "bidirectional"))
      (node (ref "X6") (pin "P1") (pinfunction "P1_P1") (pintype "bidirectional"))
    )
    (net (code "55") (name "Net-(X4-PadP2)") (class "Default")
      (node (ref "X4") (pin "P2") (pinfunction "P2_P2") (pintype "bidirectional"))
      (node (ref "X5") (pin "P2") (pinfunction "P2_P2") (pintype "bidirectional"))
      (node (ref "X6") (pin "P2") (pinfunction "P2_P2") (pintype "bidirectional"))
    )
    (net (code "56") (name "Net-(X4-PadP3)") (class "Default")
      (node (ref "X4") (pin "P3") (pinfunction "P3_P3") (pintype "bidirectional"))
      (node (ref "X5") (pin "P3") (pinfunction "P3_P3") (pintype "bidirectional"))
      (node (ref "X6") (pin "P3") (pinfunction "P3_P3") (pintype "bidirectional"))
    )
    (net (code "57") (name "Net-(X4-PadP4)") (class "Default")
      (node (ref "X4") (pin "P4") (pinfunction "P4_P4") (pintype "bidirectional"))
      (node (ref "X5") (pin "P4") (pinfunction "P4_P4") (pintype "bidirectional"))
      (node (ref "X6") (pin "P4") (pinfunction "P4_P4") (pintype "bidirectional"))
    )
    (net (code "58") (name "Net-(X4-PadP5)") (class "Default")
      (node (ref "X4") (pin "P5") (pinfunction "P5_P5") (pintype "bidirectional"))
      (node (ref "X5") (pin "P5") (pinfunction "P5_P5") (pintype "bidirectional"))
      (node (ref "X6") (pin "P5") (pinfunction "P5_P5") (pintype "bidirectional"))
    )
    (net (code "59") (name "Net-(X4-PadP6)") (class "Default")
      (node (ref "X4") (pin "P6") (pinfunction "P6_P6") (pintype "bidirectional"))
      (node (ref "X5") (pin "P6") (pinfunction "P6_P6") (pintype "bidirectional"))
      (node (ref "X6") (pin "P6") (pinfunction "P6_P6") (pintype "bidirectional"))
    )
    (net (code "60") (name "Net-(X4-PadP7)") (class "Default")
      (node (ref "X4") (pin "P7") (pinfunction "P7_P7") (pintype "bidirectional"))
      (node (ref "X5") (pin "P7") (pinfunction "P7_P7") (pintype "bidirectional"))
      (node (ref "X6") (pin "P7") (pinfunction "P7_P7") (pintype "bidirectional"))
    )
    (net (code "61") (name "Net-(X4-PadP8)") (class "Default")
      (node (ref "X4") (pin "P8") (pinfunction "P8_P8") (pintype "bidirectional"))
      (node (ref "X5") (pin "P8") (pinfunction "P8_P8") (pintype "bidirectional"))
      (node (ref "X6") (pin "P8") (pinfunction "P8_P8") (pintype "bidirectional"))
    )
    (net (code "62") (name "Net-(X4-PadP9)") (class "Default")
      (node (ref "X4") (pin "P9") (pinfunction "P9_P9") (pintype "bidirectional"))
      (node (ref "X5") (pin "P9") (pinfunction "P9_P9") (pintype "bidirectional"))
      (node (ref "X6") (pin "P9") (pinfunction "P9_P9") (pintype "bidirectional"))
    )
    (net (code "63") (name "Net-(X4-PadP10)") (class "Default")
      (node (ref "X4") (pin "P10") (pinfunction "P10_P10") (pintype "bidirectional"))
      (node (ref "X5") (pin "P10") (pinfunction "P10_P10") (pintype "bidirectional"))
      (node (ref "X6") (pin "P10") (pinfunction "P10_P10") (pintype "bidirectional"))
    )
    (net (code "64") (name "Net-(X4-PadP11)") (class "Default")
      (node (ref "X4") (pin "P11") (pinfunction "P11_P11") (pintype "bidirectional"))
      (node (ref "X5") (pin "P11") (pinfunction "P11_P11") (pintype "bidirectional"))
      (node (ref "X6") (pin "P11") (pinfunction "P11_P11") (pintype "bidirectional"))
    )
    (net (code "65") (name "Net-(X4-PadP12)") (class "Default")
      (node (ref "X4") (pin "P12") (pinfunction "P12_P12") (pintype "bidirectional"))
      (node (ref "X5") (pin "P12") (pinfunction "P12_P12") (pintype "bidirectional"))
      (node (ref "X6") (pin "P12") (pinfunction "P12_P12") (pintype "bidirectional"))
    )
    (net (code "66") (name "Net-(X4-PadP13)") (class "Default")
      (node (ref "X4") (pin "P13") (pinfunction "P13_P13") (pintype "bidirectional"))
      (node (ref "X5") (pin "P13") (pinfunction "P13_P13") (pintype "bidirectional"))
      (node (ref "X6") (pin "P13") (pinfunction "P13_P13") (pintype "bidirectional"))
    )
    (net (code "68") (name "unconnected-(J1-1-PadP1)") (class "Default")
      (node (ref "J1") (pin "P1") (pinfunction "1_P1") (pintype "passive"))
    )
    (net (code "69") (name "unconnected-(J1-2-PadP2)") (class "Default")
      (node (ref "J1") (pin "P2") (pinfunction "2_P2") (pintype "passive"))
    )
    (net (code "70") (name "unconnected-(J1-3-PadP3)") (class "Default")
      (node (ref "J1") (pin "P3") (pinfunction "3_P3") (pintype "passive"))
    )
    (net (code "71") (name "unconnected-(J1-4-PadP4)") (class "Default")
      (node (ref "J1") (pin "P4") (pinfunction "4_P4") (pintype "passive"))
    )
    (net (code "72") (name "unconnected-(J2-1-PadP1)") (class "Default")
      (node (ref "J2") (pin "P1") (pinfunction "1_P1") (pintype "passive"))
    )
    (net (code "73") (name "unconnected-(J2-2-PadP2)") (class "Default")
      (node (ref "J2") (pin "P2") (pinfunction "2_P2") (pintype "passive"))
    )
    (net (code "74") (name "unconnected-(J2-3-PadP3)") (class "Default")
      (node (ref "J2") (pin "P3") (pinfunction "3_P3") (pintype "passive"))
    )
    (net (code "75") (name "unconnected-(J2-4-PadP4)") (class "Default")
      (node (ref "J2") (pin "P4") (pinfunction "4_P4") (pintype "passive"))
    )
    (net (code "76") (name "unconnected-(J3-1-PadP1)") (class "Default")
      (node (ref "J3") (pin "P1") (pinfunction "1_P1") (pintype "passive"))
    )
    (net (code "77") (name "unconnected-(J3-2-PadP2)") (class "Default")
      (node (ref "J3") (pin "P2") (pinfunction "2_P2") (pintype "passive"))
    )
    (net (code "78") (name "unconnected-(J3-3-PadP3)") (class "Default")
      (node (ref "J3") (pin "P3") (pinfunction "3_P3") (pintype "passive"))
    )
    (net (code "79") (name "unconnected-(J3-4-PadP4)") (class "Default")
      (node (ref "J3") (pin "P4") (pinfunction "4_P4") (pintype "passive"))
    )
    (net (code "80") (name "unconnected-(J4-1-PadP1)") (class "Default")
      (node (ref "J4") (pin "P1") (pinfunction "1_P1") (pintype "passive"))
    )
    (net (code "81") (name "unconnected-(J4-2-PadP2)") (class "Default")
      (node (ref "J4") (pin "P2") (pinfunction "2_P2") (pintype "passive"))
    )
    (net (code "82") (name "unconnected-(J4-3-PadP3)") (class "Default")
      (node (ref "J4") (pin "P3") (pinfunction "3_P3") (pintype "passive"))
    )
    (net (code "83") (name "unconnected-(J4-4-PadP4)") (class "Default")
      (node (ref "J4") (pin "P4") (pinfunction "4_P4") (pintype "passive"))
    )
  )
)
